# OZ440-SE100-CAR002-SCH01_logique_-_Copie.net
KiCad netlist of a schematic drawn in Altium Designer
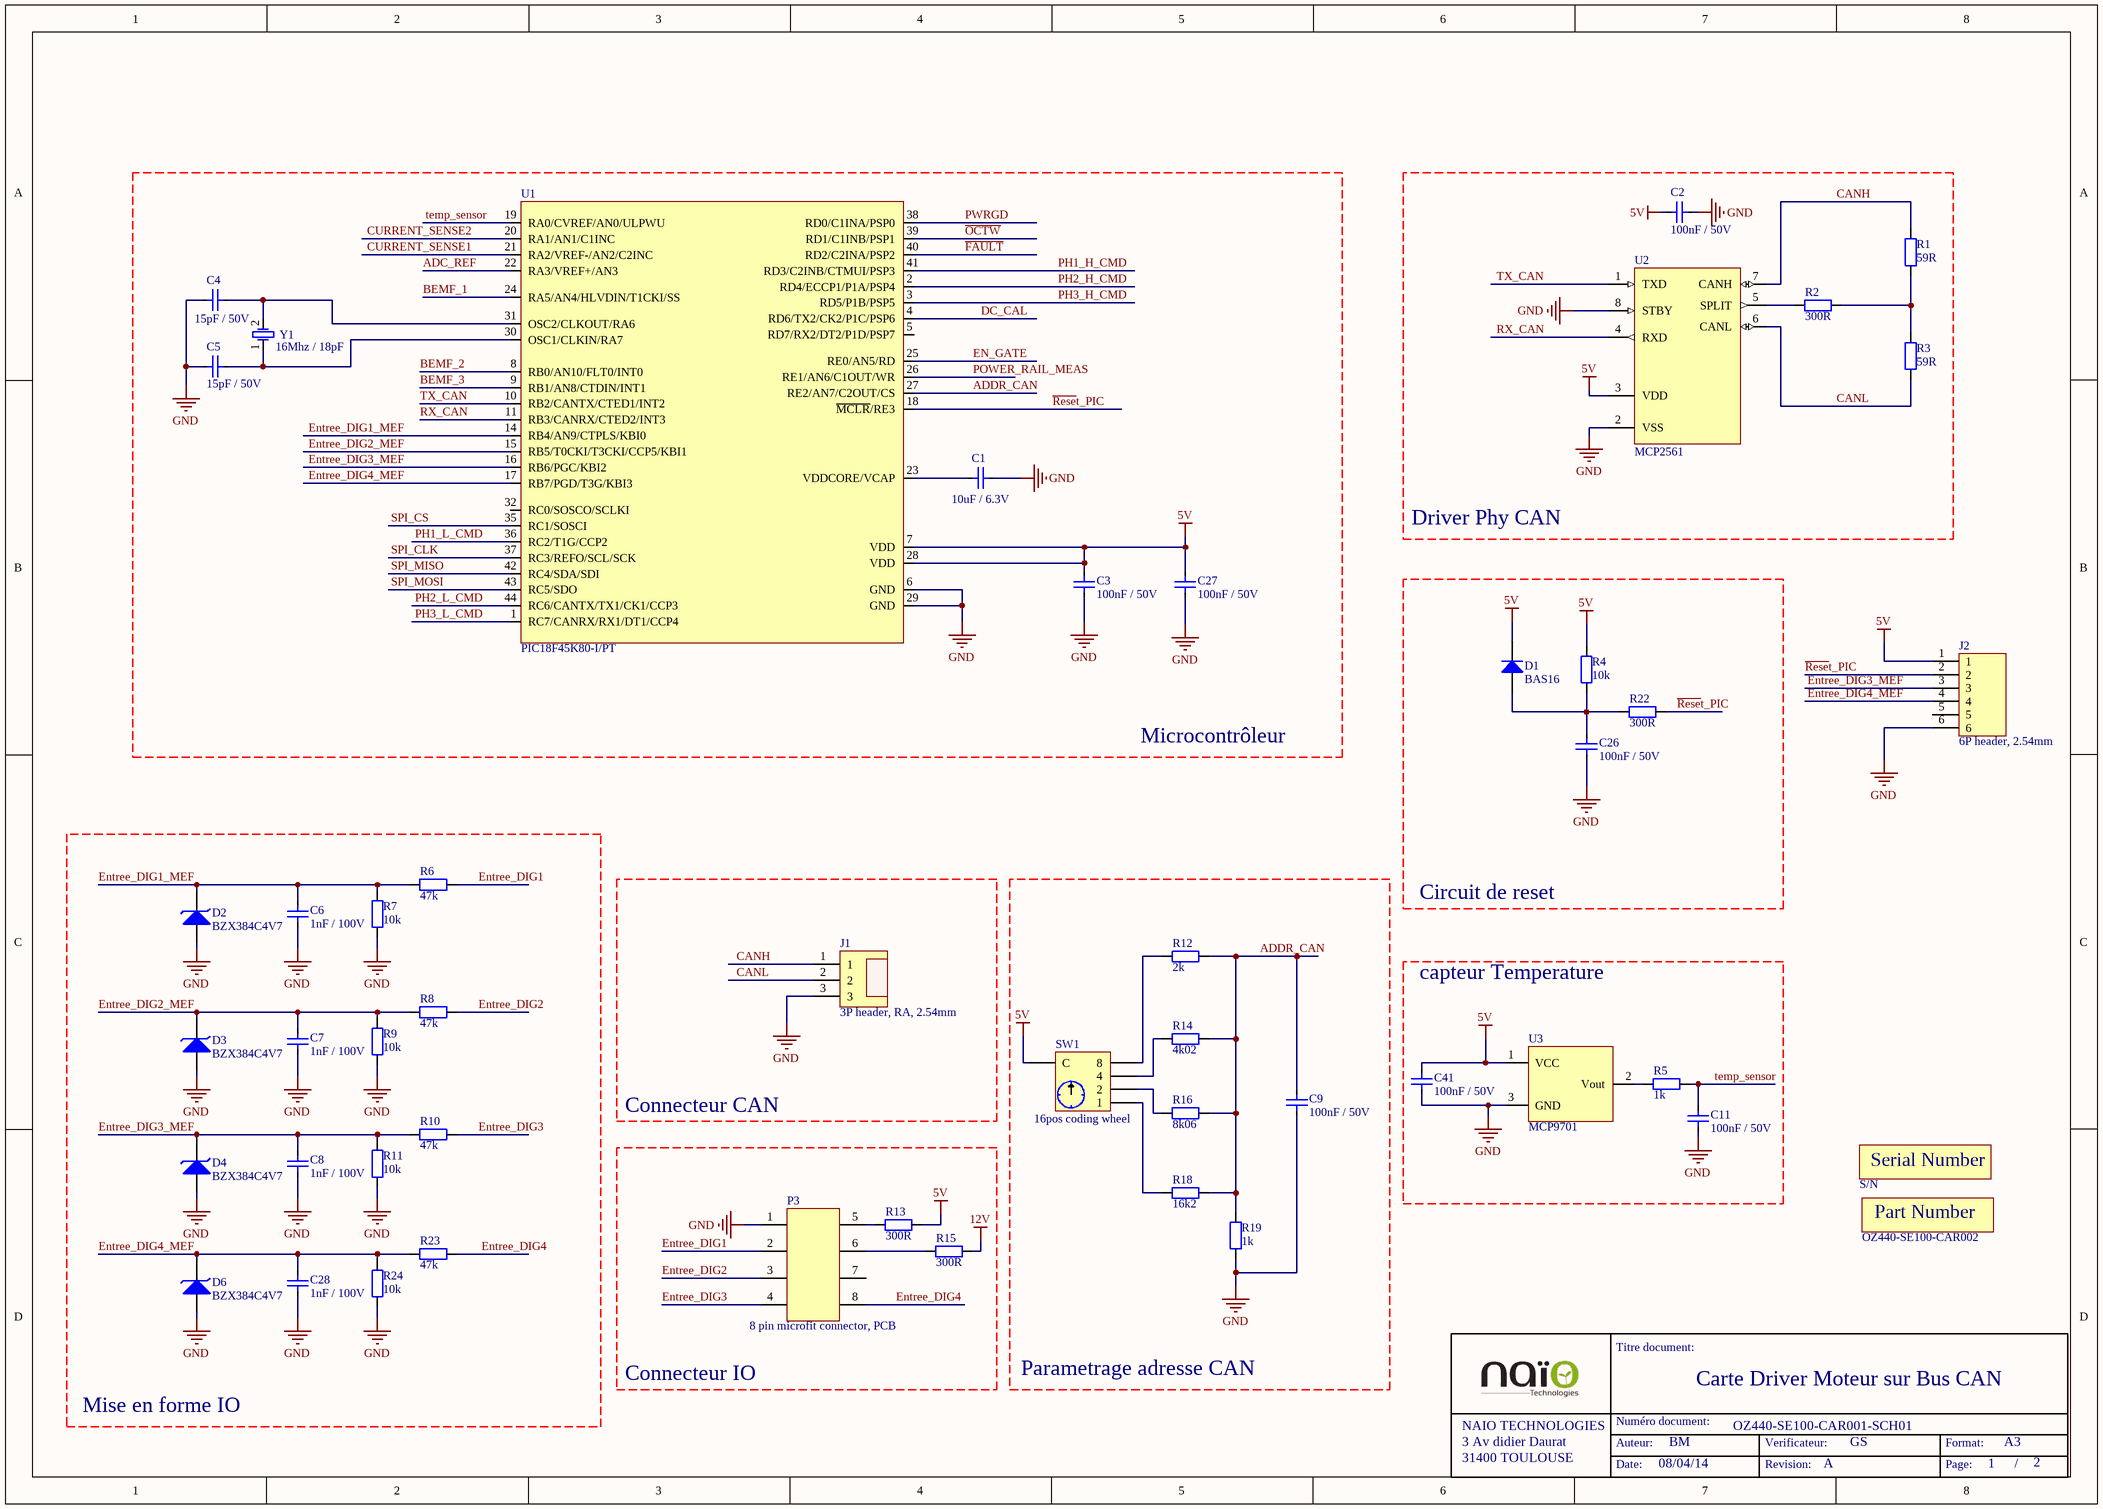
[diagram p0: OZ440-SE100-CAR002-SCH01_logique - Copie.SchDoc]

(export (version "E")
  (design (tool "Eeschema 10.0.6"))
  (components
    (comp (ref "C1")
      (value "CAP-SMD")
      (footprint "C0805-STD")
      (description "0805 10uF / 6.3V X5R ceramic capacitor")
      (fields
        (field (name "DISPLAYED REFERENCE") "10uF / 6.3V")
        (field (name "TOLERANCE") "+/- 10%")
        (field (name "MANUFACTURER") "Kemet")
      )
      (libsource (lib "lib_NAIO") (part "CAP-SMD"))
    )
    (comp (ref "C2")
      (value "CAP-SMD")
      (footprint "C0805-STD")
      (description "0805 100nF / 50V  X7R ceramic capacitor")
      (fields
        (field (name "DISPLAYED REFERENCE") "100nF / 50V")
        (field (name "TOLERANCE") "+/- 10%")
        (field (name "MANUFACTURER") "vishay")
      )
      (libsource (lib "lib_NAIO") (part "CAP-SMD"))
    )
    (comp (ref "C3")
      (value "CAP-SMD")
      (footprint "C0805-STD")
      (description "0805 100nF / 50V  X7R ceramic capacitor")
      (fields
        (field (name "DISPLAYED REFERENCE") "100nF / 50V")
        (field (name "TOLERANCE") "+/- 10%")
        (field (name "MANUFACTURER") "vishay")
      )
      (libsource (lib "lib_NAIO") (part "CAP-SMD"))
    )
    (comp (ref "C4")
      (value "CAP-SMD")
      (footprint "C0805-STD")
      (description "0805 15pF / 50V COG ceramic capacitor")
      (fields
        (field (name "DISPLAYED REFERENCE") "15pF / 50V")
        (field (name "TOLERANCE") "+/- 5%")
        (field (name "MANUFACTURER") "Kemet")
      )
      (libsource (lib "lib_NAIO") (part "CAP-SMD"))
    )
    (comp (ref "C5")
      (value "CAP-SMD")
      (footprint "C0805-STD")
      (description "0805 15pF / 50V COG ceramic capacitor")
      (fields
        (field (name "DISPLAYED REFERENCE") "15pF / 50V")
        (field (name "TOLERANCE") "+/- 5%")
        (field (name "MANUFACTURER") "Kemet")
      )
      (libsource (lib "lib_NAIO") (part "CAP-SMD"))
    )
    (comp (ref "C6")
      (value "CAP-SMD")
      (footprint "C0805-STD")
      (description "0805 1nF / 100V X7R ceramic capacitor")
      (fields
        (field (name "DISPLAYED REFERENCE") "1nF / 100V")
        (field (name "TOLERANCE") "+/- 10%")
        (field (name "MANUFACTURER") "vishay")
      )
      (libsource (lib "lib_NAIO") (part "CAP-SMD"))
    )
    (comp (ref "C7")
      (value "CAP-SMD")
      (footprint "C0805-STD")
      (description "0805 1nF / 100V X7R ceramic capacitor")
      (fields
        (field (name "DISPLAYED REFERENCE") "1nF / 100V")
        (field (name "TOLERANCE") "+/- 10%")
        (field (name "MANUFACTURER") "vishay")
      )
      (libsource (lib "lib_NAIO") (part "CAP-SMD"))
    )
    (comp (ref "C8")
      (value "CAP-SMD")
      (footprint "C0805-STD")
      (description "0805 1nF / 100V X7R ceramic capacitor")
      (fields
        (field (name "DISPLAYED REFERENCE") "1nF / 100V")
        (field (name "TOLERANCE") "+/- 10%")
        (field (name "MANUFACTURER") "vishay")
      )
      (libsource (lib "lib_NAIO") (part "CAP-SMD"))
    )
    (comp (ref "C9")
      (value "CAP-SMD")
      (footprint "C0805-STD")
      (description "0805 100nF / 50V  X7R ceramic capacitor")
      (fields
        (field (name "DISPLAYED REFERENCE") "100nF / 50V")
        (field (name "TOLERANCE") "+/- 10%")
        (field (name "MANUFACTURER") "vishay")
      )
      (libsource (lib "lib_NAIO") (part "CAP-SMD"))
    )
    (comp (ref "C11")
      (value "CAP-SMD")
      (footprint "C0805-STD")
      (description "0805 100nF / 50V  X7R ceramic capacitor")
      (fields
        (field (name "DISPLAYED REFERENCE") "100nF / 50V")
        (field (name "TOLERANCE") "+/- 10%")
        (field (name "MANUFACTURER") "vishay")
      )
      (libsource (lib "lib_NAIO") (part "CAP-SMD"))
    )
    (comp (ref "C26")
      (value "CAP-SMD")
      (footprint "C0805-STD")
      (description "0805 100nF / 50V  X7R ceramic capacitor")
      (fields
        (field (name "DISPLAYED REFERENCE") "100nF / 50V")
        (field (name "TOLERANCE") "+/- 10%")
        (field (name "MANUFACTURER") "vishay")
      )
      (libsource (lib "lib_NAIO") (part "CAP-SMD"))
    )
    (comp (ref "C27")
      (value "CAP-SMD")
      (footprint "C0805-STD")
      (description "0805 100nF / 50V  X7R ceramic capacitor")
      (fields
        (field (name "DISPLAYED REFERENCE") "100nF / 50V")
        (field (name "TOLERANCE") "+/- 10%")
        (field (name "MANUFACTURER") "vishay")
      )
      (libsource (lib "lib_NAIO") (part "CAP-SMD"))
    )
    (comp (ref "C28")
      (value "CAP-SMD")
      (footprint "C0805-STD")
      (description "0805 1nF / 100V X7R ceramic capacitor")
      (fields
        (field (name "DISPLAYED REFERENCE") "1nF / 100V")
        (field (name "TOLERANCE") "+/- 10%")
        (field (name "MANUFACTURER") "vishay")
      )
      (libsource (lib "lib_NAIO") (part "CAP-SMD"))
    )
    (comp (ref "C41")
      (value "CAP-SMD")
      (footprint "C0805-STD")
      (description "0805 100nF / 50V  X7R ceramic capacitor")
      (fields
        (field (name "DISPLAYED REFERENCE") "100nF / 50V")
        (field (name "TOLERANCE") "+/- 10%")
        (field (name "MANUFACTURER") "vishay")
      )
      (libsource (lib "lib_NAIO") (part "CAP-SMD"))
    )
    (comp (ref "D1")
      (value "BAS16-SOT23")
      (footprint "SOT23-STD")
      (description "100V / 120mA signal  diode")
      (fields (field (name "DISPLAYED REFERENCE") "BAS16") (field (name "MANUFACTURER") "NXP"))
      (libsource (lib "lib_NAIO") (part "BAS16-SOT23"))
    )
    (comp (ref "D2")
      (value "DIODE_ZENER-SOD323")
      (footprint "SOD323-SPE-BZX384")
      (description "4.7V zener diode")
      (fields (field (name "DISPLAYED REFERENCE") "BZX384C4V7") (field (name "MANUFACTURER") "VISHAY"))
      (libsource (lib "lib_NAIO") (part "DIODE_ZENER-SOD323"))
    )
    (comp (ref "D3")
      (value "DIODE_ZENER-SOD323")
      (footprint "SOD323-SPE-BZX384")
      (description "4.7V zener diode")
      (fields (field (name "DISPLAYED REFERENCE") "BZX384C4V7") (field (name "MANUFACTURER") "VISHAY"))
      (libsource (lib "lib_NAIO") (part "DIODE_ZENER-SOD323"))
    )
    (comp (ref "D4")
      (value "DIODE_ZENER-SOD323")
      (footprint "SOD323-SPE-BZX384")
      (description "4.7V zener diode")
      (fields (field (name "DISPLAYED REFERENCE") "BZX384C4V7") (field (name "MANUFACTURER") "VISHAY"))
      (libsource (lib "lib_NAIO") (part "DIODE_ZENER-SOD323"))
    )
    (comp (ref "D6")
      (value "DIODE_ZENER-SOD323")
      (footprint "SOD323-SPE-BZX384")
      (description "4.7V zener diode")
      (fields (field (name "DISPLAYED REFERENCE") "BZX384C4V7") (field (name "MANUFACTURER") "VISHAY"))
      (libsource (lib "lib_NAIO") (part "DIODE_ZENER-SOD323"))
    )
    (comp (ref "J1")
      (value "CONN-STD-3P_1ROW")
      (footprint "CONN-SPE_MOLEX_0015913033")
      (description "3 pin , 2.54mm SMD header")
      (fields
        (field (name "DISPLAYED REFERENCE") "3P header, RA, 2.54mm")
        (field (name "MANUFACTURER") "Molex")
      )
      (libsource (lib "lib_NAIO") (part "CONN-STD-3P_1ROW"))
    )
    (comp (ref "J2")
      (value "CONN-STD-6P_1ROW")
      (footprint "6P_HEADER-STD_TH_1ROW")
      (description "6P, 1 row, 2.54mm header")
      (fields (field (name "DISPLAYED REFERENCE") "6P header, 2.54mm") (field (name "MANUFACTURER") "FCI"))
      (libsource (lib "lib_NAIO") (part "CONN-STD-6P_1ROW"))
    )
    (comp (ref "P3")
      (value "CONN-SPE-8P_MOLEX_43045-0801")
      (footprint "CONN-SPE_MOLEX_43045-0801")
      (description "8 pin Microfit connector")
      (fields
        (field (name "DISPLAYED REFERENCE") "8 pin microfit connector, PCB")
        (field (name "MANUFACTURER") "Molex")
      )
      (libsource (lib "lib_NAIO") (part "CONN-SPE-8P_MOLEX_43045-0801"))
    )
    (comp (ref "PN1")
      (value "PART-NUMBER")
      (footprint "PART_NUMBER-STD")
      (description "large part number copper identification")
      (libsource (lib "lib_NAIO") (part "PART-NUMBER"))
    )
    (comp (ref "R1")
      (value "RES-SMD")
      (footprint "R0805-STD")
      (description "59 Ohm 0805 SMD resistor")
      (fields
        (field (name "DISPLAYED REFERENCE") "59R")
        (field (name "TOLERANCE") "1 %")
        (field (name "MANUFACTURER") "Vishay")
      )
      (libsource (lib "lib_NAIO") (part "RES-SMD"))
    )
    (comp (ref "R2")
      (value "RES-SMD")
      (footprint "R0805-STD")
      (description "300 ohm 0805 SMD resistor")
      (fields
        (field (name "DISPLAYED REFERENCE") "300R")
        (field (name "TOLERANCE") "1%")
        (field (name "MANUFACTURER") "Vishay")
      )
      (libsource (lib "") (part "RES-SMD_1"))
    )
    (comp (ref "R3")
      (value "RES-SMD")
      (footprint "R0805-STD")
      (description "59 Ohm 0805 SMD resistor")
      (fields
        (field (name "DISPLAYED REFERENCE") "59R")
        (field (name "TOLERANCE") "1 %")
        (field (name "MANUFACTURER") "Vishay")
      )
      (libsource (lib "lib_NAIO") (part "RES-SMD"))
    )
    (comp (ref "R4")
      (value "RES-SMD")
      (footprint "R0805-STD")
      (description "10k Ohm 0805 SMD resistor")
      (fields
        (field (name "DISPLAYED REFERENCE") "10k")
        (field (name "TOLERANCE") "1 %")
        (field (name "MANUFACTURER") "Vishay")
      )
      (libsource (lib "lib_NAIO") (part "RES-SMD"))
    )
    (comp (ref "R5")
      (value "RES-SMD")
      (footprint "R0805-STD")
      (description "1k Ohm 0805 SMD resistor")
      (fields
        (field (name "DISPLAYED REFERENCE") "1k")
        (field (name "TOLERANCE") "1 %")
        (field (name "MANUFACTURER") "Vishay")
      )
      (libsource (lib "") (part "RES-SMD_1"))
    )
    (comp (ref "R6")
      (value "RES-SMD")
      (footprint "R0805-STD")
      (description "47k Ohm 0805 SMD resistor")
      (fields
        (field (name "DISPLAYED REFERENCE") "47k")
        (field (name "TOLERANCE") "1 %")
        (field (name "MANUFACTURER") "Vishay")
      )
      (libsource (lib "") (part "RES-SMD_2"))
    )
    (comp (ref "R7")
      (value "RES-SMD")
      (footprint "R0805-STD")
      (description "10k Ohm 0805 SMD resistor")
      (fields
        (field (name "DISPLAYED REFERENCE") "10k")
        (field (name "TOLERANCE") "1 %")
        (field (name "MANUFACTURER") "Vishay")
      )
      (libsource (lib "lib_NAIO") (part "RES-SMD"))
    )
    (comp (ref "R8")
      (value "RES-SMD")
      (footprint "R0805-STD")
      (description "47k Ohm 0805 SMD resistor")
      (fields
        (field (name "DISPLAYED REFERENCE") "47k")
        (field (name "TOLERANCE") "1 %")
        (field (name "MANUFACTURER") "Vishay")
      )
      (libsource (lib "") (part "RES-SMD_2"))
    )
    (comp (ref "R9")
      (value "RES-SMD")
      (footprint "R0805-STD")
      (description "10k Ohm 0805 SMD resistor")
      (fields
        (field (name "DISPLAYED REFERENCE") "10k")
        (field (name "TOLERANCE") "1 %")
        (field (name "MANUFACTURER") "Vishay")
      )
      (libsource (lib "lib_NAIO") (part "RES-SMD"))
    )
    (comp (ref "R10")
      (value "RES-SMD")
      (footprint "R0805-STD")
      (description "47k Ohm 0805 SMD resistor")
      (fields
        (field (name "DISPLAYED REFERENCE") "47k")
        (field (name "TOLERANCE") "1 %")
        (field (name "MANUFACTURER") "Vishay")
      )
      (libsource (lib "") (part "RES-SMD_2"))
    )
    (comp (ref "R11")
      (value "RES-SMD")
      (footprint "R0805-STD")
      (description "10k Ohm 0805 SMD resistor")
      (fields
        (field (name "DISPLAYED REFERENCE") "10k")
        (field (name "TOLERANCE") "1 %")
        (field (name "MANUFACTURER") "Vishay")
      )
      (libsource (lib "lib_NAIO") (part "RES-SMD"))
    )
    (comp (ref "R12")
      (value "RES-SMD")
      (footprint "R0805-STD")
      (description "2k Ohm 0805 SMD resistor")
      (fields
        (field (name "DISPLAYED REFERENCE") "2k")
        (field (name "TOLERANCE") "1%")
        (field (name "MANUFACTURER") "Vishay")
      )
      (libsource (lib "") (part "RES-SMD_1"))
    )
    (comp (ref "R13")
      (value "RES-SMD")
      (footprint "R0805-STD")
      (description "300 ohm 0805 SMD resistor")
      (fields
        (field (name "DISPLAYED REFERENCE") "300R")
        (field (name "TOLERANCE") "1%")
        (field (name "MANUFACTURER") "Vishay")
      )
      (libsource (lib "") (part "RES-SMD_1"))
    )
    (comp (ref "R14")
      (value "RES-SMD")
      (footprint "R0805-STD")
      (description "4k02 Ohm 0805 SMD resistor")
      (fields
        (field (name "DISPLAYED REFERENCE") "4k02")
        (field (name "TOLERANCE") "1%")
        (field (name "MANUFACTURER") "Vishay")
      )
      (libsource (lib "") (part "RES-SMD_1"))
    )
    (comp (ref "R15")
      (value "RES-SMD")
      (footprint "R0805-STD")
      (description "300 ohm 0805 SMD resistor")
      (fields
        (field (name "DISPLAYED REFERENCE") "300R")
        (field (name "TOLERANCE") "1%")
        (field (name "MANUFACTURER") "Vishay")
      )
      (libsource (lib "") (part "RES-SMD_1"))
    )
    (comp (ref "R16")
      (value "RES-SMD")
      (footprint "R0805-STD")
      (description "8k06 Ohm 0805 SMD resistor")
      (fields
        (field (name "DISPLAYED REFERENCE") "8k06")
        (field (name "TOLERANCE") "1%")
        (field (name "MANUFACTURER") "Vishay")
      )
      (libsource (lib "") (part "RES-SMD_1"))
    )
    (comp (ref "R18")
      (value "RES-SMD")
      (footprint "R0805-STD")
      (description "16k2 Ohm 0805 SMD resistor")
      (fields
        (field (name "DISPLAYED REFERENCE") "16k2")
        (field (name "TOLERANCE") "1%")
        (field (name "MANUFACTURER") "Vishay")
      )
      (libsource (lib "") (part "RES-SMD_1"))
    )
    (comp (ref "R19")
      (value "RES-SMD")
      (footprint "R0805-STD")
      (description "1k Ohm 0805 SMD resistor")
      (fields
        (field (name "DISPLAYED REFERENCE") "1k")
        (field (name "TOLERANCE") "1 %")
        (field (name "MANUFACTURER") "Vishay")
      )
      (libsource (lib "lib_NAIO") (part "RES-SMD"))
    )
    (comp (ref "R22")
      (value "RES-SMD")
      (footprint "R0805-STD")
      (description "300 ohm 0805 SMD resistor")
      (fields
        (field (name "DISPLAYED REFERENCE") "300R")
        (field (name "TOLERANCE") "1%")
        (field (name "MANUFACTURER") "Vishay")
      )
      (libsource (lib "") (part "RES-SMD_1"))
    )
    (comp (ref "R23")
      (value "RES-SMD")
      (footprint "R0805-STD")
      (description "47k Ohm 0805 SMD resistor")
      (fields
        (field (name "DISPLAYED REFERENCE") "47k")
        (field (name "TOLERANCE") "1 %")
        (field (name "MANUFACTURER") "Vishay")
      )
      (libsource (lib "") (part "RES-SMD_2"))
    )
    (comp (ref "R24")
      (value "RES-SMD")
      (footprint "R0805-STD")
      (description "10k Ohm 0805 SMD resistor")
      (fields
        (field (name "DISPLAYED REFERENCE") "10k")
        (field (name "TOLERANCE") "1 %")
        (field (name "MANUFACTURER") "Vishay")
      )
      (libsource (lib "lib_NAIO") (part "RES-SMD"))
    )
    (comp (ref "SN1")
      (value "SERIAL-NUMBER")
      (footprint "SERIAL_NUMBER-STD")
      (description "serial number copper identification")
      (fields (field (name "DISPLAYED REFERENCE") "S/N"))
      (libsource (lib "lib_NAIO") (part "SERIAL-NUMBER"))
    )
    (comp (ref "SW1")
      (value "Switch-STD-coding_wheel")
      (footprint "SW-SPE-CTS_220-AMA16")
      (description "16 positions rotary dip switch")
      (fields (field (name "DISPLAYED REFERENCE") "16pos coding wheel") (field (name "MANUFACTURER") "CTS"))
      (libsource (lib "lib_NAIO") (part "Switch-STD-coding_wheel"))
    )
    (comp (ref "U1")
      (value "P18F45K80-TQFP44")
      (footprint "TQFP44-SPE-PIC18F45k80")
      (description "Pic microcontroller with embeded CAN controller")
      (fields
        (field (name "DISPLAYED REFERENCE") "PIC18F45K80-I/PT")
        (field (name "MANUFACTURER") "MICROCHIP")
      )
      (libsource (lib "lib_NAIO") (part "P18F45K80-TQFP44"))
    )
    (comp (ref "U2")
      (value "MCP2561-SOIC08")
      (footprint "SO8-SPE-MCP2561")
      (description "CAN transceiver with common mode stabilisation")
      (fields (field (name "DISPLAYED REFERENCE") "MCP2561") (field (name "MANUFACTURER") "Microchip"))
      (libsource (lib "lib_NAIO") (part "MCP2561-SOIC08"))
    )
    (comp (ref "U3")
      (value "MCP97XX-SOT23")
      (footprint "SOT23-STD")
      (description "temperature sensor with voltage output")
      (fields (field (name "DISPLAYED REFERENCE") "MCP9701") (field (name "MANUFACTURER") "Microchip"))
      (libsource (lib "lib_NAIO") (part "MCP97XX-SOT23"))
    )
    (comp (ref "Y1")
      (value "XTAL-SMD")
      (footprint "XTAL-SPE-HC49_SMD")
      (description "16Mhz Crystal")
      (fields (field (name "DISPLAYED REFERENCE") "16Mhz / 18pF") (field (name "MANUFACTURER") "Multicomp"))
      (libsource (lib "lib_NAIO") (part "XTAL-SMD"))
    )
  )
  (nets
    (net (code "1") (name "/ADC_REF") (class "Default")
      (node (ref "U1") (pin "22") (pinfunction "RA3/VREF+/AN3_22") (pintype "passive"))
    )
    (net (code "2") (name "/ADDR_CAN") (class "Default")
      (node (ref "C9") (pin "2") (pinfunction "2_2") (pintype "passive"))
      (node (ref "R12") (pin "2") (pinfunction "2_2") (pintype "passive"))
      (node (ref "R14") (pin "2") (pinfunction "2_2") (pintype "passive"))
      (node (ref "R16") (pin "2") (pinfunction "2_2") (pintype "passive"))
      (node (ref "R18") (pin "2") (pinfunction "2_2") (pintype "passive"))
      (node (ref "R19") (pin "2") (pinfunction "2_2") (pintype "passive"))
      (node (ref "U1") (pin "27") (pinfunction "RE2/AN7/C2OUT/CS_27") (pintype "passive"))
    )
    (net (code "3") (name "/BEMF_1") (class "Default")
      (node (ref "U1") (pin "24") (pinfunction "RA5/AN4/HLVDIN/T1CKI/SS_24") (pintype "passive"))
    )
    (net (code "4") (name "/BEMF_2") (class "Default")
      (node (ref "U1") (pin "8") (pinfunction "RB0/AN10/FLT0/INT0_8") (pintype "passive"))
    )
    (net (code "5") (name "/BEMF_3") (class "Default")
      (node (ref "U1") (pin "9") (pinfunction "RB1/AN8/CTDIN/INT1_9") (pintype "passive"))
    )
    (net (code "6") (name "/CANH") (class "Default")
      (node (ref "J1") (pin "1") (pinfunction "1_1") (pintype "passive"))
      (node (ref "R1") (pin "2") (pinfunction "2_2") (pintype "passive"))
      (node (ref "U2") (pin "7") (pinfunction "CANH_7") (pintype "bidirectional"))
    )
    (net (code "7") (name "/CANL") (class "Default")
      (node (ref "J1") (pin "2") (pinfunction "2_2") (pintype "passive"))
      (node (ref "R3") (pin "1") (pinfunction "1_1") (pintype "passive"))
      (node (ref "U2") (pin "6") (pinfunction "CANL_6") (pintype "bidirectional"))
    )
    (net (code "8") (name "/CURRENT_SENSE1") (class "Default")
      (node (ref "U1") (pin "21") (pinfunction "RA2/VREF-/AN2/C2INC_21") (pintype "passive"))
    )
    (net (code "9") (name "/CURRENT_SENSE2") (class "Default")
      (node (ref "U1") (pin "20") (pinfunction "RA1/AN1/C1INC_20") (pintype "passive"))
    )
    (net (code "10") (name "/DC_CAL") (class "Default")
      (node (ref "U1") (pin "4") (pinfunction "RD6/TX2/CK2/P1C/PSP6_4") (pintype "passive"))
    )
    (net (code "11") (name "/EN_GATE") (class "Default")
      (node (ref "U1") (pin "25") (pinfunction "RE0/AN5/RD_25") (pintype "passive"))
    )
    (net (code "12") (name "/Entree_DIG1") (class "Default")
      (node (ref "P3") (pin "2") (pinfunction "2_2") (pintype "passive"))
      (node (ref "R6") (pin "1") (pinfunction "1_1") (pintype "passive"))
    )
    (net (code "13") (name "/Entree_DIG1_MEF") (class "Default")
      (node (ref "C6") (pin "2") (pinfunction "2_2") (pintype "passive"))
      (node (ref "D2") (pin "K") (pinfunction "K_K") (pintype "passive"))
      (node (ref "R6") (pin "2") (pinfunction "2_2") (pintype "passive"))
      (node (ref "R7") (pin "2") (pinfunction "2_2") (pintype "passive"))
      (node (ref "U1") (pin "14") (pinfunction "RB4/AN9/CTPLS/KBI0_14") (pintype "passive"))
    )
    (net (code "14") (name "/Entree_DIG2") (class "Default")
      (node (ref "P3") (pin "3") (pinfunction "3_3") (pintype "passive"))
      (node (ref "R8") (pin "1") (pinfunction "1_1") (pintype "passive"))
    )
    (net (code "15") (name "/Entree_DIG2_MEF") (class "Default")
      (node (ref "C7") (pin "2") (pinfunction "2_2") (pintype "passive"))
      (node (ref "D3") (pin "K") (pinfunction "K_K") (pintype "passive"))
      (node (ref "R8") (pin "2") (pinfunction "2_2") (pintype "passive"))
      (node (ref "R9") (pin "2") (pinfunction "2_2") (pintype "passive"))
      (node (ref "U1") (pin "15") (pinfunction "RB5/T0CKI/T3CKI/CCP5/KBI1_15") (pintype "passive"))
    )
    (net (code "16") (name "/Entree_DIG3") (class "Default")
      (node (ref "P3") (pin "4") (pinfunction "7_4") (pintype "passive"))
      (node (ref "R10") (pin "1") (pinfunction "1_1") (pintype "passive"))
    )
    (net (code "17") (name "/Entree_DIG3_MEF") (class "Default")
      (node (ref "C8") (pin "2") (pinfunction "2_2") (pintype "passive"))
      (node (ref "D4") (pin "K") (pinfunction "K_K") (pintype "passive"))
      (node (ref "J2") (pin "3") (pinfunction "3_3") (pintype "passive"))
      (node (ref "R10") (pin "2") (pinfunction "2_2") (pintype "passive"))
      (node (ref "R11") (pin "2") (pinfunction "2_2") (pintype "passive"))
      (node (ref "U1") (pin "16") (pinfunction "RB6/PGC/KBI2_16") (pintype "passive"))
    )
    (net (code "18") (name "/Entree_DIG4") (class "Default")
      (node (ref "P3") (pin "8") (pinfunction "8_8") (pintype "passive"))
      (node (ref "R23") (pin "1") (pinfunction "1_1") (pintype "passive"))
    )
    (net (code "19") (name "/Entree_DIG4_MEF") (class "Default")
      (node (ref "C28") (pin "2") (pinfunction "2_2") (pintype "passive"))
      (node (ref "D6") (pin "K") (pinfunction "K_K") (pintype "passive"))
      (node (ref "J2") (pin "4") (pinfunction "4_4") (pintype "passive"))
      (node (ref "R23") (pin "2") (pinfunction "2_2") (pintype "passive"))
      (node (ref "R24") (pin "2") (pinfunction "2_2") (pintype "passive"))
      (node (ref "U1") (pin "17") (pinfunction "RB7/PGD/T3G/KBI3_17") (pintype "passive"))
    )
    (net (code "20") (name "/PH1_H_CMD") (class "Default")
      (node (ref "U1") (pin "41") (pinfunction "RD3/C2INB/CTMUI/PSP3_41") (pintype "passive"))
    )
    (net (code "21") (name "/PH1_L_CMD") (class "Default")
      (node (ref "U1") (pin "36") (pinfunction "RC2/T1G/CCP2_36") (pintype "passive"))
    )
    (net (code "22") (name "/PH2_H_CMD") (class "Default")
      (node (ref "U1") (pin "2") (pinfunction "RD4/ECCP1/P1A/PSP4_2") (pintype "passive"))
    )
    (net (code "23") (name "/PH2_L_CMD") (class "Default")
      (node (ref "U1") (pin "44") (pinfunction "RC6/CANTX/TX1/CK1/CCP3_44") (pintype "passive"))
    )
    (net (code "24") (name "/PH3_H_CMD") (class "Default")
      (node (ref "U1") (pin "3") (pinfunction "RD5/P1B/PSP5_3") (pintype "passive"))
    )
    (net (code "25") (name "/PH3_L_CMD") (class "Default")
      (node (ref "U1") (pin "1") (pinfunction "RC7/CANRX/RX1/DT1/CCP4_1") (pintype "passive"))
    )
    (net (code "26") (name "/POWER_RAIL_MEAS") (class "Default")
      (node (ref "U1") (pin "26") (pinfunction "RE1/AN6/C1OUT/WR_26") (pintype "passive"))
    )
    (net (code "27") (name "/PWRGD") (class "Default")
      (node (ref "U1") (pin "38") (pinfunction "RD0/C1INA/PSP0_38") (pintype "passive"))
    )
    (net (code "28") (name "/RX_CAN") (class "Default")
      (node (ref "U1") (pin "11") (pinfunction "RB3/CANRX/CTED2/INT3_11") (pintype "passive"))
      (node (ref "U2") (pin "4") (pinfunction "RXD_4") (pintype "output"))
    )
    (net (code "29") (name "/SPI_CLK") (class "Default")
      (node (ref "U1") (pin "37") (pinfunction "RC3/REFO/SCL/SCK_37") (pintype "passive"))
    )
    (net (code "30") (name "/SPI_CS") (class "Default")
      (node (ref "U1") (pin "35") (pinfunction "RC1/SOSCI_35") (pintype "passive"))
    )
    (net (code "31") (name "/SPI_MISO") (class "Default")
      (node (ref "U1") (pin "42") (pinfunction "RC4/SDA/SDI_42") (pintype "passive"))
    )
    (net (code "32") (name "/SPI_MOSI") (class "Default")
      (node (ref "U1") (pin "43") (pinfunction "RC5/SDO_43") (pintype "passive"))
    )
    (net (code "33") (name "/TX_CAN") (class "Default")
      (node (ref "U1") (pin "10") (pinfunction "RB2/CANTX/CTED1/INT2_10") (pintype "passive"))
      (node (ref "U2") (pin "1") (pinfunction "TXD_1") (pintype "input"))
    )
    (net (code "34") (name "/temp_sensor") (class "Default")
      (node (ref "C11") (pin "2") (pinfunction "2_2") (pintype "passive"))
      (node (ref "R5") (pin "2") (pinfunction "2_2") (pintype "passive"))
      (node (ref "U1") (pin "19") (pinfunction "RA0/CVREF/AN0/ULPWU_19") (pintype "passive"))
    )
    (net (code "35") (name "/~{FAULT}") (class "Default")
      (node (ref "U1") (pin "40") (pinfunction "RD2/C2INA/PSP2_40") (pintype "passive"))
    )
    (net (code "36") (name "/~{OCTW}") (class "Default")
      (node (ref "U1") (pin "39") (pinfunction "RD1/C1INB/PSP1_39") (pintype "passive"))
    )
    (net (code "37") (name "/~{Rese}t_PIC") (class "Default")
      (node (ref "J2") (pin "2") (pinfunction "2_2") (pintype "passive"))
      (node (ref "R22") (pin "2") (pinfunction "2_2") (pintype "passive"))
      (node (ref "U1") (pin "18") (pinfunction "~{MCLR}/RE3_18") (pintype "passive"))
    )
    (net (code "38") (name "5V") (class "Default")
      (node (ref "C2") (pin "2") (pinfunction "2_2") (pintype "passive"))
      (node (ref "C27") (pin "2") (pinfunction "2_2") (pintype "passive"))
      (node (ref "C3") (pin "2") (pinfunction "2_2") (pintype "passive"))
      (node (ref "C41") (pin "2") (pinfunction "2_2") (pintype "passive"))
      (node (ref "D1") (pin "3") (pinfunction "K_3") (pintype "passive"))
      (node (ref "J2") (pin "1") (pinfunction "1_1") (pintype "passive"))
      (node (ref "R13") (pin "2") (pinfunction "2_2") (pintype "passive"))
      (node (ref "R4") (pin "2") (pinfunction "2_2") (pintype "passive"))
      (node (ref "SW1") (pin "C") (pinfunction "C_C") (pintype "passive"))
      (node (ref "U1") (pin "28") (pinfunction "VDD_28") (pintype "passive"))
      (node (ref "U1") (pin "7") (pinfunction "VDD_7") (pintype "passive"))
      (node (ref "U2") (pin "3") (pinfunction "VDD_3") (pintype "power_in"))
      (node (ref "U3") (pin "1") (pinfunction "VCC_1") (pintype "power_in"))
    )
    (net (code "39") (name "12V") (class "Default")
      (node (ref "R15") (pin "2") (pinfunction "2_2") (pintype "passive"))
    )
    (net (code "40") (name "GND") (class "Default")
      (node (ref "C1") (pin "2") (pinfunction "2_2") (pintype "passive"))
      (node (ref "C11") (pin "1") (pinfunction "1_1") (pintype "passive"))
      (node (ref "C2") (pin "1") (pinfunction "1_1") (pintype "passive"))
      (node (ref "C26") (pin "1") (pinfunction "1_1") (pintype "passive"))
      (node (ref "C27") (pin "1") (pinfunction "1_1") (pintype "passive"))
      (node (ref "C28") (pin "1") (pinfunction "1_1") (pintype "passive"))
      (node (ref "C3") (pin "1") (pinfunction "1_1") (pintype "passive"))
      (node (ref "C4") (pin "1") (pinfunction "1_1") (pintype "passive"))
      (node (ref "C41") (pin "1") (pinfunction "1_1") (pintype "passive"))
      (node (ref "C5") (pin "1") (pinfunction "1_1") (pintype "passive"))
      (node (ref "C6") (pin "1") (pinfunction "1_1") (pintype "passive"))
      (node (ref "C7") (pin "1") (pinfunction "1_1") (pintype "passive"))
      (node (ref "C8") (pin "1") (pinfunction "1_1") (pintype "passive"))
      (node (ref "C9") (pin "1") (pinfunction "1_1") (pintype "passive"))
      (node (ref "D2") (pin "A") (pinfunction "A_A") (pintype "passive"))
      (node (ref "D3") (pin "A") (pinfunction "A_A") (pintype "passive"))
      (node (ref "D4") (pin "A") (pinfunction "A_A") (pintype "passive"))
      (node (ref "D6") (pin "A") (pinfunction "A_A") (pintype "passive"))
      (node (ref "J1") (pin "3") (pinfunction "3_3") (pintype "passive"))
      (node (ref "J2") (pin "6") (pinfunction "6_6") (pintype "passive"))
      (node (ref "P3") (pin "1") (pinfunction "1_1") (pintype "passive"))
      (node (ref "R11") (pin "1") (pinfunction "1_1") (pintype "passive"))
      (node (ref "R19") (pin "1") (pinfunction "1_1") (pintype "passive"))
      (node (ref "R24") (pin "1") (pinfunction "1_1") (pintype "passive"))
      (node (ref "R7") (pin "1") (pinfunction "1_1") (pintype "passive"))
      (node (ref "R9") (pin "1") (pinfunction "1_1") (pintype "passive"))
      (node (ref "U1") (pin "29") (pinfunction "GND_29") (pintype "passive"))
      (node (ref "U1") (pin "6") (pinfunction "GND_6") (pintype "passive"))
      (node (ref "U2") (pin "2") (pinfunction "VSS_2") (pintype "power_in"))
      (node (ref "U2") (pin "8") (pinfunction "STBY_8") (pintype "input"))
      (node (ref "U3") (pin "3") (pinfunction "GND_3") (pintype "power_in"))
    )
    (net (code "41") (name "Net-(D1-A)") (class "Default")
      (node (ref "C26") (pin "2") (pinfunction "2_2") (pintype "passive"))
      (node (ref "D1") (pin "1") (pinfunction "A_1") (pintype "passive"))
      (node (ref "R22") (pin "1") (pinfunction "1_1") (pintype "passive"))
      (node (ref "R4") (pin "1") (pinfunction "1_1") (pintype "passive"))
    )
    (net (code "42") (name "Net-(P3-9)") (class "Default")
      (node (ref "P3") (pin "5") (pinfunction "9_5") (pintype "passive"))
      (node (ref "R13") (pin "1") (pinfunction "1_1") (pintype "passive"))
    )
    (net (code "43") (name "Net-(P3-Pad6)") (class "Default")
      (node (ref "P3") (pin "6") (pinfunction "6_6") (pintype "passive"))
      (node (ref "R15") (pin "1") (pinfunction "1_1") (pintype "passive"))
    )
    (net (code "44") (name "Net-(R1-Pad1)") (class "Default")
      (node (ref "R1") (pin "1") (pinfunction "1_1") (pintype "passive"))
      (node (ref "R2") (pin "2") (pinfunction "2_2") (pintype "passive"))
      (node (ref "R3") (pin "2") (pinfunction "2_2") (pintype "passive"))
    )
    (net (code "45") (name "Net-(R12-Pad1)") (class "Default")
      (node (ref "R12") (pin "1") (pinfunction "1_1") (pintype "passive"))
      (node (ref "SW1") (pin "8") (pinfunction "8_8") (pintype "passive"))
    )
    (net (code "46") (name "Net-(R14-Pad1)") (class "Default")
      (node (ref "R14") (pin "1") (pinfunction "1_1") (pintype "passive"))
      (node (ref "SW1") (pin "4") (pinfunction "4_4") (pintype "passive"))
    )
    (net (code "47") (name "Net-(R16-Pad1)") (class "Default")
      (node (ref "R16") (pin "1") (pinfunction "1_1") (pintype "passive"))
      (node (ref "SW1") (pin "2") (pinfunction "2_2") (pintype "passive"))
    )
    (net (code "48") (name "Net-(R18-Pad1)") (class "Default")
      (node (ref "R18") (pin "1") (pinfunction "1_1") (pintype "passive"))
      (node (ref "SW1") (pin "1") (pinfunction "1_1") (pintype "passive"))
    )
    (net (code "49") (name "Net-(U1-OSC1{slash}CLKIN{slash}RA7)") (class "Default")
      (node (ref "C5") (pin "2") (pinfunction "2_2") (pintype "passive"))
      (node (ref "U1") (pin "30") (pinfunction "OSC1/CLKIN/RA7_30") (pintype "passive"))
      (node (ref "Y1") (pin "1") (pinfunction "OSC1_1") (pintype "passive"))
    )
    (net (code "50") (name "Net-(U1-OSC2{slash}CLKOUT{slash}RA6)") (class "Default")
      (node (ref "C4") (pin "2") (pinfunction "2_2") (pintype "passive"))
      (node (ref "U1") (pin "31") (pinfunction "OSC2/CLKOUT/RA6_31") (pintype "passive"))
      (node (ref "Y1") (pin "2") (pinfunction "OSC2_2") (pintype "passive"))
    )
    (net (code "51") (name "Net-(U1-VDDCORE{slash}VCAP)") (class "Default")
      (node (ref "C1") (pin "1") (pinfunction "1_1") (pintype "passive"))
      (node (ref "U1") (pin "23") (pinfunction "VDDCORE/VCAP_23") (pintype "passive"))
    )
    (net (code "52") (name "Net-(U2-SPLIT)") (class "Default")
      (node (ref "R2") (pin "1") (pinfunction "1_1") (pintype "passive"))
      (node (ref "U2") (pin "5") (pinfunction "SPLIT_5") (pintype "output"))
    )
    (net (code "53") (name "Net-(U3-Vout)") (class "Default")
      (node (ref "R5") (pin "1") (pinfunction "1_1") (pintype "passive"))
      (node (ref "U3") (pin "2") (pinfunction "Vout_2") (pintype "open_collector"))
    )
    (net (code "54") (name "unconnected-(J2-Pad5)") (class "Default")
      (node (ref "J2") (pin "5") (pinfunction "5_5") (pintype "passive"))
    )
    (net (code "55") (name "unconnected-(P3-Pad7)") (class "Default")
      (node (ref "P3") (pin "7") (pinfunction "7_7") (pintype "passive"))
    )
    (net (code "56") (name "unconnected-(U1-RC0{slash}SOSCO{slash}SCLKI-Pad32)") (class "Default")
      (node (ref "U1") (pin "32") (pinfunction "RC0/SOSCO/SCLKI_32") (pintype "passive"))
    )
    (net (code "57") (name "unconnected-(U1-RD7{slash}RX2{slash}DT2{slash}P1D{slash}PSP7-Pad5)") (class "Default")
      (node (ref "U1") (pin "5") (pinfunction "RD7/RX2/DT2/P1D/PSP7_5") (pintype "passive"))
    )
  )
)
